# AMS_Test_Board_rev1.net
KiCad netlist of a schematic drawn in EAGLE
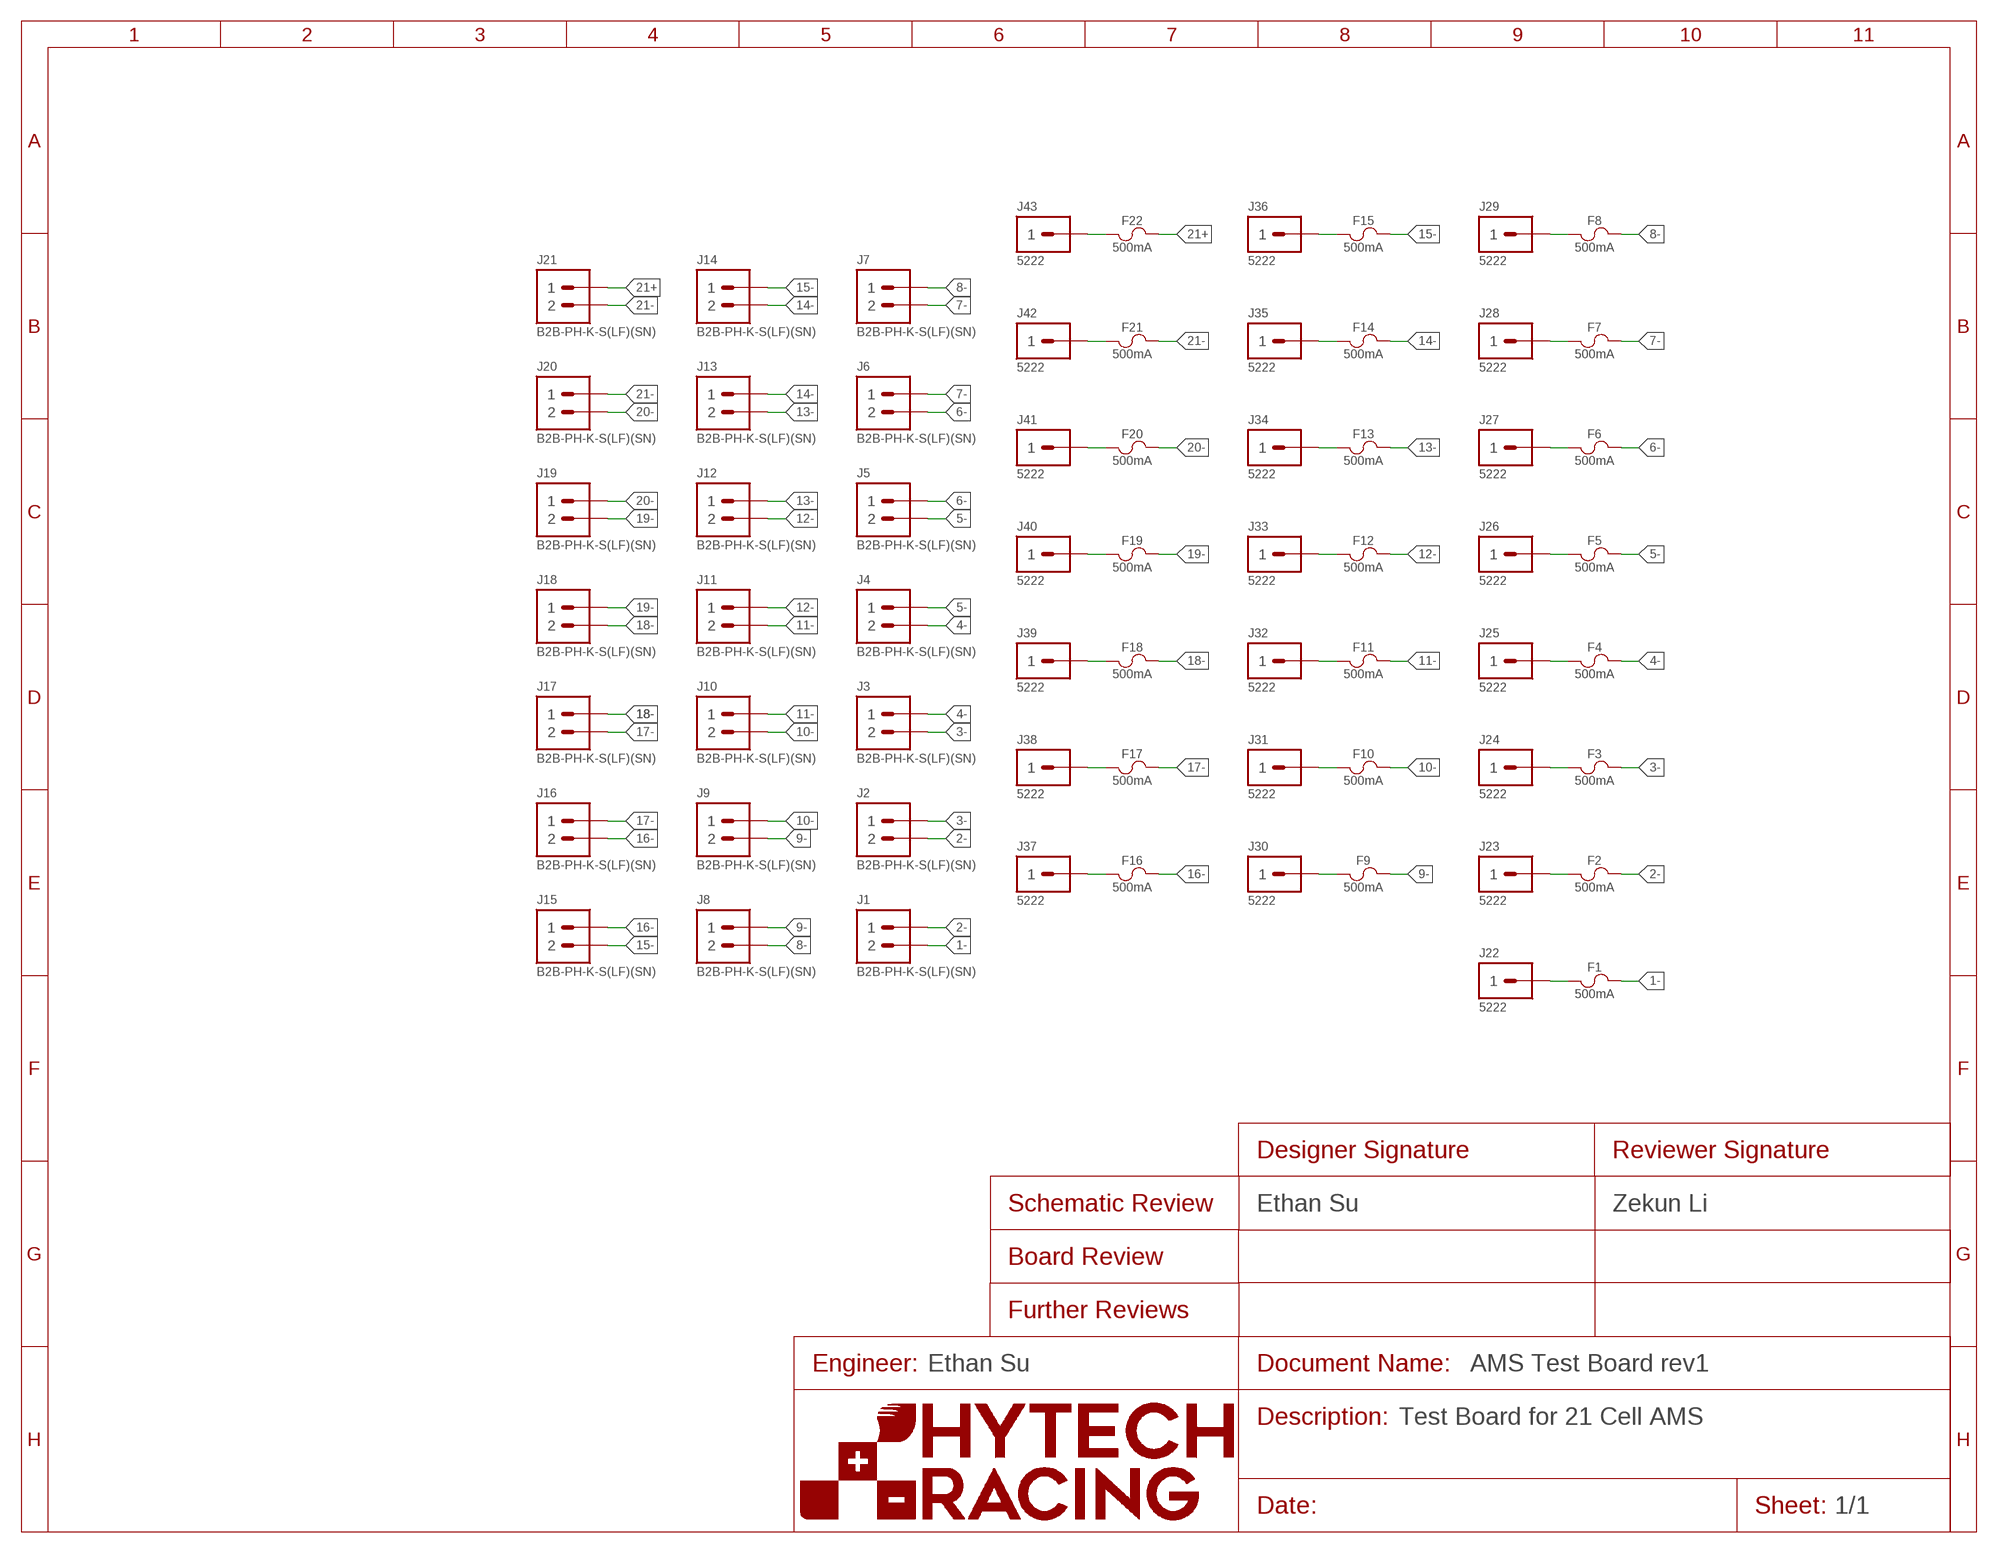
[diagram p0: schematic, sheet 1]

(export (version "E")
  (design (tool "Eeschema 10.0.6"))
  (components
    (comp (ref "F1")
      (value "FUSE_OMF_125_.5A")
      (footprint "eagle-import:OMF_125")
      (fields
        (field (name "CURRENT") "500mA")
        (field (name "MANUFACTURER") "Schurter Inc.")
        (field (name "MPN") "3404.0045.11")
        (field (name "VOLTAGE") "125V")
      )
      (libsource (lib "eagle-import") (part "FUSE_?_OMF_125.5A"))
    )
    (comp (ref "F2")
      (value "FUSE_OMF_125_.5A")
      (footprint "eagle-import:OMF_125")
      (fields
        (field (name "CURRENT") "500mA")
        (field (name "MANUFACTURER") "Schurter Inc.")
        (field (name "MPN") "3404.0045.11")
        (field (name "VOLTAGE") "125V")
      )
      (libsource (lib "eagle-import") (part "FUSE_?_OMF_125.5A"))
    )
    (comp (ref "F3")
      (value "FUSE_OMF_125_.5A")
      (footprint "eagle-import:OMF_125")
      (fields
        (field (name "CURRENT") "500mA")
        (field (name "MANUFACTURER") "Schurter Inc.")
        (field (name "MPN") "3404.0045.11")
        (field (name "VOLTAGE") "125V")
      )
      (libsource (lib "eagle-import") (part "FUSE_?_OMF_125.5A"))
    )
    (comp (ref "F4")
      (value "FUSE_OMF_125_.5A")
      (footprint "eagle-import:OMF_125")
      (fields
        (field (name "CURRENT") "500mA")
        (field (name "MANUFACTURER") "Schurter Inc.")
        (field (name "MPN") "3404.0045.11")
        (field (name "VOLTAGE") "125V")
      )
      (libsource (lib "eagle-import") (part "FUSE_?_OMF_125.5A"))
    )
    (comp (ref "F5")
      (value "FUSE_OMF_125_.5A")
      (footprint "eagle-import:OMF_125")
      (fields
        (field (name "CURRENT") "500mA")
        (field (name "MANUFACTURER") "Schurter Inc.")
        (field (name "MPN") "3404.0045.11")
        (field (name "VOLTAGE") "125V")
      )
      (libsource (lib "eagle-import") (part "FUSE_?_OMF_125.5A"))
    )
    (comp (ref "F6")
      (value "FUSE_OMF_125_.5A")
      (footprint "eagle-import:OMF_125")
      (fields
        (field (name "CURRENT") "500mA")
        (field (name "MANUFACTURER") "Schurter Inc.")
        (field (name "MPN") "3404.0045.11")
        (field (name "VOLTAGE") "125V")
      )
      (libsource (lib "eagle-import") (part "FUSE_?_OMF_125.5A"))
    )
    (comp (ref "F7")
      (value "FUSE_OMF_125_.5A")
      (footprint "eagle-import:OMF_125")
      (fields
        (field (name "CURRENT") "500mA")
        (field (name "MANUFACTURER") "Schurter Inc.")
        (field (name "MPN") "3404.0045.11")
        (field (name "VOLTAGE") "125V")
      )
      (libsource (lib "eagle-import") (part "FUSE_?_OMF_125.5A"))
    )
    (comp (ref "F8")
      (value "FUSE_OMF_125_.5A")
      (footprint "eagle-import:OMF_125")
      (fields
        (field (name "CURRENT") "500mA")
        (field (name "MANUFACTURER") "Schurter Inc.")
        (field (name "MPN") "3404.0045.11")
        (field (name "VOLTAGE") "125V")
      )
      (libsource (lib "eagle-import") (part "FUSE_?_OMF_125.5A"))
    )
    (comp (ref "F9")
      (value "FUSE_OMF_125_.5A")
      (footprint "eagle-import:OMF_125")
      (fields
        (field (name "CURRENT") "500mA")
        (field (name "MANUFACTURER") "Schurter Inc.")
        (field (name "MPN") "3404.0045.11")
        (field (name "VOLTAGE") "125V")
      )
      (libsource (lib "eagle-import") (part "FUSE_?_OMF_125.5A"))
    )
    (comp (ref "F10")
      (value "FUSE_OMF_125_.5A")
      (footprint "eagle-import:OMF_125")
      (fields
        (field (name "CURRENT") "500mA")
        (field (name "MANUFACTURER") "Schurter Inc.")
        (field (name "MPN") "3404.0045.11")
        (field (name "VOLTAGE") "125V")
      )
      (libsource (lib "eagle-import") (part "FUSE_?_OMF_125.5A"))
    )
    (comp (ref "F11")
      (value "FUSE_OMF_125_.5A")
      (footprint "eagle-import:OMF_125")
      (fields
        (field (name "CURRENT") "500mA")
        (field (name "MANUFACTURER") "Schurter Inc.")
        (field (name "MPN") "3404.0045.11")
        (field (name "VOLTAGE") "125V")
      )
      (libsource (lib "eagle-import") (part "FUSE_?_OMF_125.5A"))
    )
    (comp (ref "F12")
      (value "FUSE_OMF_125_.5A")
      (footprint "eagle-import:OMF_125")
      (fields
        (field (name "CURRENT") "500mA")
        (field (name "MANUFACTURER") "Schurter Inc.")
        (field (name "MPN") "3404.0045.11")
        (field (name "VOLTAGE") "125V")
      )
      (libsource (lib "eagle-import") (part "FUSE_?_OMF_125.5A"))
    )
    (comp (ref "F13")
      (value "FUSE_OMF_125_.5A")
      (footprint "eagle-import:OMF_125")
      (fields
        (field (name "CURRENT") "500mA")
        (field (name "MANUFACTURER") "Schurter Inc.")
        (field (name "MPN") "3404.0045.11")
        (field (name "VOLTAGE") "125V")
      )
      (libsource (lib "eagle-import") (part "FUSE_?_OMF_125.5A"))
    )
    (comp (ref "F14")
      (value "FUSE_OMF_125_.5A")
      (footprint "eagle-import:OMF_125")
      (fields
        (field (name "CURRENT") "500mA")
        (field (name "MANUFACTURER") "Schurter Inc.")
        (field (name "MPN") "3404.0045.11")
        (field (name "VOLTAGE") "125V")
      )
      (libsource (lib "eagle-import") (part "FUSE_?_OMF_125.5A"))
    )
    (comp (ref "F15")
      (value "FUSE_OMF_125_.5A")
      (footprint "eagle-import:OMF_125")
      (fields
        (field (name "CURRENT") "500mA")
        (field (name "MANUFACTURER") "Schurter Inc.")
        (field (name "MPN") "3404.0045.11")
        (field (name "VOLTAGE") "125V")
      )
      (libsource (lib "eagle-import") (part "FUSE_?_OMF_125.5A"))
    )
    (comp (ref "F16")
      (value "FUSE_OMF_125_.5A")
      (footprint "eagle-import:OMF_125")
      (fields
        (field (name "CURRENT") "500mA")
        (field (name "MANUFACTURER") "Schurter Inc.")
        (field (name "MPN") "3404.0045.11")
        (field (name "VOLTAGE") "125V")
      )
      (libsource (lib "eagle-import") (part "FUSE_?_OMF_125.5A"))
    )
    (comp (ref "F17")
      (value "FUSE_OMF_125_.5A")
      (footprint "eagle-import:OMF_125")
      (fields
        (field (name "CURRENT") "500mA")
        (field (name "MANUFACTURER") "Schurter Inc.")
        (field (name "MPN") "3404.0045.11")
        (field (name "VOLTAGE") "125V")
      )
      (libsource (lib "eagle-import") (part "FUSE_?_OMF_125.5A"))
    )
    (comp (ref "F18")
      (value "FUSE_OMF_125_.5A")
      (footprint "eagle-import:OMF_125")
      (fields
        (field (name "CURRENT") "500mA")
        (field (name "MANUFACTURER") "Schurter Inc.")
        (field (name "MPN") "3404.0045.11")
        (field (name "VOLTAGE") "125V")
      )
      (libsource (lib "eagle-import") (part "FUSE_?_OMF_125.5A"))
    )
    (comp (ref "F19")
      (value "FUSE_OMF_125_.5A")
      (footprint "eagle-import:OMF_125")
      (fields
        (field (name "CURRENT") "500mA")
        (field (name "MANUFACTURER") "Schurter Inc.")
        (field (name "MPN") "3404.0045.11")
        (field (name "VOLTAGE") "125V")
      )
      (libsource (lib "eagle-import") (part "FUSE_?_OMF_125.5A"))
    )
    (comp (ref "F20")
      (value "FUSE_OMF_125_.5A")
      (footprint "eagle-import:OMF_125")
      (fields
        (field (name "CURRENT") "500mA")
        (field (name "MANUFACTURER") "Schurter Inc.")
        (field (name "MPN") "3404.0045.11")
        (field (name "VOLTAGE") "125V")
      )
      (libsource (lib "eagle-import") (part "FUSE_?_OMF_125.5A"))
    )
    (comp (ref "F21")
      (value "FUSE_OMF_125_.5A")
      (footprint "eagle-import:OMF_125")
      (fields
        (field (name "CURRENT") "500mA")
        (field (name "MANUFACTURER") "Schurter Inc.")
        (field (name "MPN") "3404.0045.11")
        (field (name "VOLTAGE") "125V")
      )
      (libsource (lib "eagle-import") (part "FUSE_?_OMF_125.5A"))
    )
    (comp (ref "F22")
      (value "FUSE_OMF_125_.5A")
      (footprint "eagle-import:OMF_125")
      (fields
        (field (name "CURRENT") "500mA")
        (field (name "MANUFACTURER") "Schurter Inc.")
        (field (name "MPN") "3404.0045.11")
        (field (name "VOLTAGE") "125V")
      )
      (libsource (lib "eagle-import") (part "FUSE_?_OMF_125.5A"))
    )
    (comp (ref "J1")
      (value "CONNECTOR-2__B2B-PH-K")
      (footprint "eagle-import:B2B-PH-K")
      (fields
        (field (name "MANUFACTURER") "JST Sales America Inc.")
        (field (name "MPN") "B2B-PH-K-S(LF)(SN)")
      )
      (libsource (lib "eagle-import") (part "CONNECTOR-2_?_B2B-PH-K"))
    )
    (comp (ref "J2")
      (value "CONNECTOR-2__B2B-PH-K")
      (footprint "eagle-import:B2B-PH-K")
      (fields
        (field (name "MANUFACTURER") "JST Sales America Inc.")
        (field (name "MPN") "B2B-PH-K-S(LF)(SN)")
      )
      (libsource (lib "eagle-import") (part "CONNECTOR-2_?_B2B-PH-K"))
    )
    (comp (ref "J3")
      (value "CONNECTOR-2__B2B-PH-K")
      (footprint "eagle-import:B2B-PH-K")
      (fields
        (field (name "MANUFACTURER") "JST Sales America Inc.")
        (field (name "MPN") "B2B-PH-K-S(LF)(SN)")
      )
      (libsource (lib "eagle-import") (part "CONNECTOR-2_?_B2B-PH-K"))
    )
    (comp (ref "J4")
      (value "CONNECTOR-2__B2B-PH-K")
      (footprint "eagle-import:B2B-PH-K")
      (fields
        (field (name "MANUFACTURER") "JST Sales America Inc.")
        (field (name "MPN") "B2B-PH-K-S(LF)(SN)")
      )
      (libsource (lib "eagle-import") (part "CONNECTOR-2_?_B2B-PH-K"))
    )
    (comp (ref "J5")
      (value "CONNECTOR-2__B2B-PH-K")
      (footprint "eagle-import:B2B-PH-K")
      (fields
        (field (name "MANUFACTURER") "JST Sales America Inc.")
        (field (name "MPN") "B2B-PH-K-S(LF)(SN)")
      )
      (libsource (lib "eagle-import") (part "CONNECTOR-2_?_B2B-PH-K"))
    )
    (comp (ref "J6")
      (value "CONNECTOR-2__B2B-PH-K")
      (footprint "eagle-import:B2B-PH-K")
      (fields
        (field (name "MANUFACTURER") "JST Sales America Inc.")
        (field (name "MPN") "B2B-PH-K-S(LF)(SN)")
      )
      (libsource (lib "eagle-import") (part "CONNECTOR-2_?_B2B-PH-K"))
    )
    (comp (ref "J7")
      (value "CONNECTOR-2__B2B-PH-K")
      (footprint "eagle-import:B2B-PH-K")
      (fields
        (field (name "MANUFACTURER") "JST Sales America Inc.")
        (field (name "MPN") "B2B-PH-K-S(LF)(SN)")
      )
      (libsource (lib "eagle-import") (part "CONNECTOR-2_?_B2B-PH-K"))
    )
    (comp (ref "J8")
      (value "CONNECTOR-2__B2B-PH-K")
      (footprint "eagle-import:B2B-PH-K")
      (fields
        (field (name "MANUFACTURER") "JST Sales America Inc.")
        (field (name "MPN") "B2B-PH-K-S(LF)(SN)")
      )
      (libsource (lib "eagle-import") (part "CONNECTOR-2_?_B2B-PH-K"))
    )
    (comp (ref "J9")
      (value "CONNECTOR-2__B2B-PH-K")
      (footprint "eagle-import:B2B-PH-K")
      (fields
        (field (name "MANUFACTURER") "JST Sales America Inc.")
        (field (name "MPN") "B2B-PH-K-S(LF)(SN)")
      )
      (libsource (lib "eagle-import") (part "CONNECTOR-2_?_B2B-PH-K"))
    )
    (comp (ref "J10")
      (value "CONNECTOR-2__B2B-PH-K")
      (footprint "eagle-import:B2B-PH-K")
      (fields
        (field (name "MANUFACTURER") "JST Sales America Inc.")
        (field (name "MPN") "B2B-PH-K-S(LF)(SN)")
      )
      (libsource (lib "eagle-import") (part "CONNECTOR-2_?_B2B-PH-K"))
    )
    (comp (ref "J11")
      (value "CONNECTOR-2__B2B-PH-K")
      (footprint "eagle-import:B2B-PH-K")
      (fields
        (field (name "MANUFACTURER") "JST Sales America Inc.")
        (field (name "MPN") "B2B-PH-K-S(LF)(SN)")
      )
      (libsource (lib "eagle-import") (part "CONNECTOR-2_?_B2B-PH-K"))
    )
    (comp (ref "J12")
      (value "CONNECTOR-2__B2B-PH-K")
      (footprint "eagle-import:B2B-PH-K")
      (fields
        (field (name "MANUFACTURER") "JST Sales America Inc.")
        (field (name "MPN") "B2B-PH-K-S(LF)(SN)")
      )
      (libsource (lib "eagle-import") (part "CONNECTOR-2_?_B2B-PH-K"))
    )
    (comp (ref "J13")
      (value "CONNECTOR-2__B2B-PH-K")
      (footprint "eagle-import:B2B-PH-K")
      (fields
        (field (name "MANUFACTURER") "JST Sales America Inc.")
        (field (name "MPN") "B2B-PH-K-S(LF)(SN)")
      )
      (libsource (lib "eagle-import") (part "CONNECTOR-2_?_B2B-PH-K"))
    )
    (comp (ref "J14")
      (value "CONNECTOR-2__B2B-PH-K")
      (footprint "eagle-import:B2B-PH-K")
      (fields
        (field (name "MANUFACTURER") "JST Sales America Inc.")
        (field (name "MPN") "B2B-PH-K-S(LF)(SN)")
      )
      (libsource (lib "eagle-import") (part "CONNECTOR-2_?_B2B-PH-K"))
    )
    (comp (ref "J15")
      (value "CONNECTOR-2__B2B-PH-K")
      (footprint "eagle-import:B2B-PH-K")
      (fields
        (field (name "MANUFACTURER") "JST Sales America Inc.")
        (field (name "MPN") "B2B-PH-K-S(LF)(SN)")
      )
      (libsource (lib "eagle-import") (part "CONNECTOR-2_?_B2B-PH-K"))
    )
    (comp (ref "J16")
      (value "CONNECTOR-2__B2B-PH-K")
      (footprint "eagle-import:B2B-PH-K")
      (fields
        (field (name "MANUFACTURER") "JST Sales America Inc.")
        (field (name "MPN") "B2B-PH-K-S(LF)(SN)")
      )
      (libsource (lib "eagle-import") (part "CONNECTOR-2_?_B2B-PH-K"))
    )
    (comp (ref "J17")
      (value "CONNECTOR-2__B2B-PH-K")
      (footprint "eagle-import:B2B-PH-K")
      (fields
        (field (name "MANUFACTURER") "JST Sales America Inc.")
        (field (name "MPN") "B2B-PH-K-S(LF)(SN)")
      )
      (libsource (lib "eagle-import") (part "CONNECTOR-2_?_B2B-PH-K"))
    )
    (comp (ref "J18")
      (value "CONNECTOR-2__B2B-PH-K")
      (footprint "eagle-import:B2B-PH-K")
      (fields
        (field (name "MANUFACTURER") "JST Sales America Inc.")
        (field (name "MPN") "B2B-PH-K-S(LF)(SN)")
      )
      (libsource (lib "eagle-import") (part "CONNECTOR-2_?_B2B-PH-K"))
    )
    (comp (ref "J19")
      (value "CONNECTOR-2__B2B-PH-K")
      (footprint "eagle-import:B2B-PH-K")
      (fields
        (field (name "MANUFACTURER") "JST Sales America Inc.")
        (field (name "MPN") "B2B-PH-K-S(LF)(SN)")
      )
      (libsource (lib "eagle-import") (part "CONNECTOR-2_?_B2B-PH-K"))
    )
    (comp (ref "J20")
      (value "CONNECTOR-2__B2B-PH-K")
      (footprint "eagle-import:B2B-PH-K")
      (fields
        (field (name "MANUFACTURER") "JST Sales America Inc.")
        (field (name "MPN") "B2B-PH-K-S(LF)(SN)")
      )
      (libsource (lib "eagle-import") (part "CONNECTOR-2_?_B2B-PH-K"))
    )
    (comp (ref "J21")
      (value "CONNECTOR-2__B2B-PH-K")
      (footprint "eagle-import:B2B-PH-K")
      (fields
        (field (name "MANUFACTURER") "JST Sales America Inc.")
        (field (name "MPN") "B2B-PH-K-S(LF)(SN)")
      )
      (libsource (lib "eagle-import") (part "CONNECTOR-2_?_B2B-PH-K"))
    )
    (comp (ref "J22")
      (value "CONNECTOR-1_5222")
      (footprint "eagle-import:5222")
      (fields (field (name "MPN") "5222") (field (name "MANUFACTURER") "Keystone Electronics"))
      (libsource (lib "eagle-import") (part "CONNECTOR-1_?5222"))
    )
    (comp (ref "J23")
      (value "CONNECTOR-1_5222")
      (footprint "eagle-import:5222")
      (fields (field (name "MPN") "5222") (field (name "MANUFACTURER") "Keystone Electronics"))
      (libsource (lib "eagle-import") (part "CONNECTOR-1_?5222"))
    )
    (comp (ref "J24")
      (value "CONNECTOR-1_5222")
      (footprint "eagle-import:5222")
      (fields (field (name "MPN") "5222") (field (name "MANUFACTURER") "Keystone Electronics"))
      (libsource (lib "eagle-import") (part "CONNECTOR-1_?5222"))
    )
    (comp (ref "J25")
      (value "CONNECTOR-1_5222")
      (footprint "eagle-import:5222")
      (fields (field (name "MPN") "5222") (field (name "MANUFACTURER") "Keystone Electronics"))
      (libsource (lib "eagle-import") (part "CONNECTOR-1_?5222"))
    )
    (comp (ref "J26")
      (value "CONNECTOR-1_5222")
      (footprint "eagle-import:5222")
      (fields (field (name "MPN") "5222") (field (name "MANUFACTURER") "Keystone Electronics"))
      (libsource (lib "eagle-import") (part "CONNECTOR-1_?5222"))
    )
    (comp (ref "J27")
      (value "CONNECTOR-1_5222")
      (footprint "eagle-import:5222")
      (fields (field (name "MPN") "5222") (field (name "MANUFACTURER") "Keystone Electronics"))
      (libsource (lib "eagle-import") (part "CONNECTOR-1_?5222"))
    )
    (comp (ref "J28")
      (value "CONNECTOR-1_5222")
      (footprint "eagle-import:5222")
      (fields (field (name "MPN") "5222") (field (name "MANUFACTURER") "Keystone Electronics"))
      (libsource (lib "eagle-import") (part "CONNECTOR-1_?5222"))
    )
    (comp (ref "J29")
      (value "CONNECTOR-1_5222")
      (footprint "eagle-import:5222")
      (fields (field (name "MPN") "5222") (field (name "MANUFACTURER") "Keystone Electronics"))
      (libsource (lib "eagle-import") (part "CONNECTOR-1_?5222"))
    )
    (comp (ref "J30")
      (value "CONNECTOR-1_5222")
      (footprint "eagle-import:5222")
      (fields (field (name "MPN") "5222") (field (name "MANUFACTURER") "Keystone Electronics"))
      (libsource (lib "eagle-import") (part "CONNECTOR-1_?5222"))
    )
    (comp (ref "J31")
      (value "CONNECTOR-1_5222")
      (footprint "eagle-import:5222")
      (fields (field (name "MPN") "5222") (field (name "MANUFACTURER") "Keystone Electronics"))
      (libsource (lib "eagle-import") (part "CONNECTOR-1_?5222"))
    )
    (comp (ref "J32")
      (value "CONNECTOR-1_5222")
      (footprint "eagle-import:5222")
      (fields (field (name "MPN") "5222") (field (name "MANUFACTURER") "Keystone Electronics"))
      (libsource (lib "eagle-import") (part "CONNECTOR-1_?5222"))
    )
    (comp (ref "J33")
      (value "CONNECTOR-1_5222")
      (footprint "eagle-import:5222")
      (fields (field (name "MPN") "5222") (field (name "MANUFACTURER") "Keystone Electronics"))
      (libsource (lib "eagle-import") (part "CONNECTOR-1_?5222"))
    )
    (comp (ref "J34")
      (value "CONNECTOR-1_5222")
      (footprint "eagle-import:5222")
      (fields (field (name "MPN") "5222") (field (name "MANUFACTURER") "Keystone Electronics"))
      (libsource (lib "eagle-import") (part "CONNECTOR-1_?5222"))
    )
    (comp (ref "J35")
      (value "CONNECTOR-1_5222")
      (footprint "eagle-import:5222")
      (fields (field (name "MPN") "5222") (field (name "MANUFACTURER") "Keystone Electronics"))
      (libsource (lib "eagle-import") (part "CONNECTOR-1_?5222"))
    )
    (comp (ref "J36")
      (value "CONNECTOR-1_5222")
      (footprint "eagle-import:5222")
      (fields (field (name "MPN") "5222") (field (name "MANUFACTURER") "Keystone Electronics"))
      (libsource (lib "eagle-import") (part "CONNECTOR-1_?5222"))
    )
    (comp (ref "J37")
      (value "CONNECTOR-1_5222")
      (footprint "eagle-import:5222")
      (fields (field (name "MPN") "5222") (field (name "MANUFACTURER") "Keystone Electronics"))
      (libsource (lib "eagle-import") (part "CONNECTOR-1_?5222"))
    )
    (comp (ref "J38")
      (value "CONNECTOR-1_5222")
      (footprint "eagle-import:5222")
      (fields (field (name "MPN") "5222") (field (name "MANUFACTURER") "Keystone Electronics"))
      (libsource (lib "eagle-import") (part "CONNECTOR-1_?5222"))
    )
    (comp (ref "J39")
      (value "CONNECTOR-1_5222")
      (footprint "eagle-import:5222")
      (fields (field (name "MPN") "5222") (field (name "MANUFACTURER") "Keystone Electronics"))
      (libsource (lib "eagle-import") (part "CONNECTOR-1_?5222"))
    )
    (comp (ref "J40")
      (value "CONNECTOR-1_5222")
      (footprint "eagle-import:5222")
      (fields (field (name "MPN") "5222") (field (name "MANUFACTURER") "Keystone Electronics"))
      (libsource (lib "eagle-import") (part "CONNECTOR-1_?5222"))
    )
    (comp (ref "J41")
      (value "CONNECTOR-1_5222")
      (footprint "eagle-import:5222")
      (fields (field (name "MPN") "5222") (field (name "MANUFACTURER") "Keystone Electronics"))
      (libsource (lib "eagle-import") (part "CONNECTOR-1_?5222"))
    )
    (comp (ref "J42")
      (value "CONNECTOR-1_5222")
      (footprint "eagle-import:5222")
      (fields (field (name "MPN") "5222") (field (name "MANUFACTURER") "Keystone Electronics"))
      (libsource (lib "eagle-import") (part "CONNECTOR-1_?5222"))
    )
    (comp (ref "J43")
      (value "CONNECTOR-1_5222")
      (footprint "eagle-import:5222")
      (fields (field (name "MPN") "5222") (field (name "MANUFACTURER") "Keystone Electronics"))
      (libsource (lib "eagle-import") (part "CONNECTOR-1_?5222"))
    )
  )
  (nets
    (net (code "1") (name "1-") (class "Default")
      (node (ref "F1") (pin "2") (pinfunction "2_2") (pintype "passive"))
      (node (ref "J1") (pin "2") (pinfunction "2_2") (pintype "passive"))
    )
    (net (code "2") (name "2-") (class "Default")
      (node (ref "F2") (pin "2") (pinfunction "2_2") (pintype "passive"))
      (node (ref "J1") (pin "1") (pinfunction "1_1") (pintype "passive"))
      (node (ref "J2") (pin "2") (pinfunction "2_2") (pintype "passive"))
    )
    (net (code "3") (name "3-") (class "Default")
      (node (ref "F3") (pin "2") (pinfunction "2_2") (pintype "passive"))
      (node (ref "J2") (pin "1") (pinfunction "1_1") (pintype "passive"))
      (node (ref "J3") (pin "2") (pinfunction "2_2") (pintype "passive"))
    )
    (net (code "4") (name "4-") (class "Default")
      (node (ref "F4") (pin "2") (pinfunction "2_2") (pintype "passive"))
      (node (ref "J3") (pin "1") (pinfunction "1_1") (pintype "passive"))
      (node (ref "J4") (pin "2") (pinfunction "2_2") (pintype "passive"))
    )
    (net (code "5") (name "5-") (class "Default")
      (node (ref "F5") (pin "2") (pinfunction "2_2") (pintype "passive"))
      (node (ref "J4") (pin "1") (pinfunction "1_1") (pintype "passive"))
      (node (ref "J5") (pin "2") (pinfunction "2_2") (pintype "passive"))
    )
    (net (code "6") (name "6-") (class "Default")
      (node (ref "F6") (pin "2") (pinfunction "2_2") (pintype "passive"))
      (node (ref "J5") (pin "1") (pinfunction "1_1") (pintype "passive"))
      (node (ref "J6") (pin "2") (pinfunction "2_2") (pintype "passive"))
    )
    (net (code "7") (name "7-") (class "Default")
      (node (ref "F7") (pin "2") (pinfunction "2_2") (pintype "passive"))
      (node (ref "J6") (pin "1") (pinfunction "1_1") (pintype "passive"))
      (node (ref "J7") (pin "2") (pinfunction "2_2") (pintype "passive"))
    )
    (net (code "8") (name "8-") (class "Default")
      (node (ref "F8") (pin "2") (pinfunction "2_2") (pintype "passive"))
      (node (ref "J7") (pin "1") (pinfunction "1_1") (pintype "passive"))
      (node (ref "J8") (pin "2") (pinfunction "2_2") (pintype "passive"))
    )
    (net (code "9") (name "9-") (class "Default")
      (node (ref "F9") (pin "2") (pinfunction "2_2") (pintype "passive"))
      (node (ref "J8") (pin "1") (pinfunction "1_1") (pintype "passive"))
      (node (ref "J9") (pin "2") (pinfunction "2_2") (pintype "passive"))
    )
    (net (code "10") (name "10-") (class "Default")
      (node (ref "F10") (pin "2") (pinfunction "2_2") (pintype "passive"))
      (node (ref "J10") (pin "2") (pinfunction "2_2") (pintype "passive"))
      (node (ref "J9") (pin "1") (pinfunction "1_1") (pintype "passive"))
    )
    (net (code "11") (name "11-") (class "Default")
      (node (ref "F11") (pin "2") (pinfunction "2_2") (pintype "passive"))
      (node (ref "J10") (pin "1") (pinfunction "1_1") (pintype "passive"))
      (node (ref "J11") (pin "2") (pinfunction "2_2") (pintype "passive"))
    )
    (net (code "12") (name "12-") (class "Default")
      (node (ref "F12") (pin "2") (pinfunction "2_2") (pintype "passive"))
      (node (ref "J11") (pin "1") (pinfunction "1_1") (pintype "passive"))
      (node (ref "J12") (pin "2") (pinfunction "2_2") (pintype "passive"))
    )
    (net (code "13") (name "13-") (class "Default")
      (node (ref "F13") (pin "2") (pinfunction "2_2") (pintype "passive"))
      (node (ref "J12") (pin "1") (pinfunction "1_1") (pintype "passive"))
      (node (ref "J13") (pin "2") (pinfunction "2_2") (pintype "passive"))
    )
    (net (code "14") (name "14-") (class "Default")
      (node (ref "F14") (pin "2") (pinfunction "2_2") (pintype "passive"))
      (node (ref "J13") (pin "1") (pinfunction "1_1") (pintype "passive"))
      (node (ref "J14") (pin "2") (pinfunction "2_2") (pintype "passive"))
    )
    (net (code "15") (name "15-") (class "Default")
      (node (ref "F15") (pin "2") (pinfunction "2_2") (pintype "passive"))
      (node (ref "J14") (pin "1") (pinfunction "1_1") (pintype "passive"))
      (node (ref "J15") (pin "2") (pinfunction "2_2") (pintype "passive"))
    )
    (net (code "16") (name "16-") (class "Default")
      (node (ref "F16") (pin "2") (pinfunction "2_2") (pintype "passive"))
      (node (ref "J15") (pin "1") (pinfunction "1_1") (pintype "passive"))
      (node (ref "J16") (pin "2") (pinfunction "2_2") (pintype "passive"))
    )
    (net (code "17") (name "17-") (class "Default")
      (node (ref "F17") (pin "2") (pinfunction "2_2") (pintype "passive"))
      (node (ref "J16") (pin "1") (pinfunction "1_1") (pintype "passive"))
      (node (ref "J17") (pin "2") (pinfunction "2_2") (pintype "passive"))
    )
    (net (code "18") (name "18-") (class "Default")
      (node (ref "F18") (pin "2") (pinfunction "2_2") (pintype "passive"))
      (node (ref "J17") (pin "1") (pinfunction "1_1") (pintype "passive"))
      (node (ref "J18") (pin "2") (pinfunction "2_2") (pintype "passive"))
    )
    (net (code "19") (name "19-") (class "Default")
      (node (ref "F19") (pin "2") (pinfunction "2_2") (pintype "passive"))
      (node (ref "J18") (pin "1") (pinfunction "1_1") (pintype "passive"))
      (node (ref "J19") (pin "2") (pinfunction "2_2") (pintype "passive"))
    )
    (net (code "20") (name "20-") (class "Default")
      (node (ref "F20") (pin "2") (pinfunction "2_2") (pintype "passive"))
      (node (ref "J19") (pin "1") (pinfunction "1_1") (pintype "passive"))
      (node (ref "J20") (pin "2") (pinfunction "2_2") (pintype "passive"))
    )
    (net (code "21") (name "21+") (class "Default")
      (node (ref "F22") (pin "2") (pinfunction "2_2") (pintype "passive"))
      (node (ref "J21") (pin "1") (pinfunction "1_1") (pintype "passive"))
    )
    (net (code "22") (name "21-") (class "Default")
      (node (ref "F21") (pin "2") (pinfunction "2_2") (pintype "passive"))
      (node (ref "J20") (pin "1") (pinfunction "1_1") (pintype "passive"))
      (node (ref "J21") (pin "2") (pinfunction "2_2") (pintype "passive"))
    )
    (net (code "23") (name "Net-(F1-Pad1)") (class "Default")
      (node (ref "F1") (pin "1") (pinfunction "1_1") (pintype "passive"))
      (node (ref "J22") (pin "1") (pinfunction "1_1") (pintype "passive"))
    )
    (net (code "24") (name "Net-(F2-Pad1)") (class "Default")
      (node (ref "F2") (pin "1") (pinfunction "1_1") (pintype "passive"))
      (node (ref "J23") (pin "1") (pinfunction "1_1") (pintype "passive"))
    )
    (net (code "25") (name "Net-(F3-Pad1)") (class "Default")
      (node (ref "F3") (pin "1") (pinfunction "1_1") (pintype "passive"))
      (node (ref "J24") (pin "1") (pinfunction "1_1") (pintype "passive"))
    )
    (net (code "26") (name "Net-(F4-Pad1)") (class "Default")
      (node (ref "F4") (pin "1") (pinfunction "1_1") (pintype "passive"))
      (node (ref "J25") (pin "1") (pinfunction "1_1") (pintype "passive"))
    )
    (net (code "27") (name "Net-(F5-Pad1)") (class "Default")
      (node (ref "F5") (pin "1") (pinfunction "1_1") (pintype "passive"))
      (node (ref "J26") (pin "1") (pinfunction "1_1") (pintype "passive"))
    )
    (net (code "28") (name "Net-(F6-Pad1)") (class "Default")
      (node (ref "F6") (pin "1") (pinfunction "1_1") (pintype "passive"))
      (node (ref "J27") (pin "1") (pinfunction "1_1") (pintype "passive"))
    )
    (net (code "29") (name "Net-(F7-Pad1)") (class "Default")
      (node (ref "F7") (pin "1") (pinfunction "1_1") (pintype "passive"))
      (node (ref "J28") (pin "1") (pinfunction "1_1") (pintype "passive"))
    )
    (net (code "30") (name "Net-(F8-Pad1)") (class "Default")
      (node (ref "F8") (pin "1") (pinfunction "1_1") (pintype "passive"))
      (node (ref "J29") (pin "1") (pinfunction "1_1") (pintype "passive"))
    )
    (net (code "31") (name "Net-(F9-Pad1)") (class "Default")
      (node (ref "F9") (pin "1") (pinfunction "1_1") (pintype "passive"))
      (node (ref "J30") (pin "1") (pinfunction "1_1") (pintype "passive"))
    )
    (net (code "32") (name "Net-(F10-Pad1)") (class "Default")
      (node (ref "F10") (pin "1") (pinfunction "1_1") (pintype "passive"))
      (node (ref "J31") (pin "1") (pinfunction "1_1") (pintype "passive"))
    )
    (net (code "33") (name "Net-(F11-Pad1)") (class "Default")
      (node (ref "F11") (pin "1") (pinfunction "1_1") (pintype "passive"))
      (node (ref "J32") (pin "1") (pinfunction "1_1") (pintype "passive"))
    )
    (net (code "34") (name "Net-(F12-Pad1)") (class "Default")
      (node (ref "F12") (pin "1") (pinfunction "1_1") (pintype "passive"))
      (node (ref "J33") (pin "1") (pinfunction "1_1") (pintype "passive"))
    )
    (net (code "35") (name "Net-(F13-Pad1)") (class "Default")
      (node (ref "F13") (pin "1") (pinfunction "1_1") (pintype "passive"))
      (node (ref "J34") (pin "1") (pinfunction "1_1") (pintype "passive"))
    )
    (net (code "36") (name "Net-(F14-Pad1)") (class "Default")
      (node (ref "F14") (pin "1") (pinfunction "1_1") (pintype "passive"))
      (node (ref "J35") (pin "1") (pinfunction "1_1") (pintype "passive"))
    )
    (net (code "37") (name "Net-(F15-Pad1)") (class "Default")
      (node (ref "F15") (pin "1") (pinfunction "1_1") (pintype "passive"))
      (node (ref "J36") (pin "1") (pinfunction "1_1") (pintype "passive"))
    )
    (net (code "38") (name "Net-(F16-Pad1)") (class "Default")
      (node (ref "F16") (pin "1") (pinfunction "1_1") (pintype "passive"))
      (node (ref "J37") (pin "1") (pinfunction "1_1") (pintype "passive"))
    )
    (net (code "39") (name "Net-(F17-Pad1)") (class "Default")
      (node (ref "F17") (pin "1") (pinfunction "1_1") (pintype "passive"))
      (node (ref "J38") (pin "1") (pinfunction "1_1") (pintype "passive"))
    )
    (net (code "40") (name "Net-(F18-Pad1)") (class "Default")
      (node (ref "F18") (pin "1") (pinfunction "1_1") (pintype "passive"))
      (node (ref "J39") (pin "1") (pinfunction "1_1") (pintype "passive"))
    )
    (net (code "41") (name "Net-(F19-Pad1)") (class "Default")
      (node (ref "F19") (pin "1") (pinfunction "1_1") (pintype "passive"))
      (node (ref "J40") (pin "1") (pinfunction "1_1") (pintype "passive"))
    )
    (net (code "42") (name "Net-(F20-Pad1)") (class "Default")
      (node (ref "F20") (pin "1") (pinfunction "1_1") (pintype "passive"))
      (node (ref "J41") (pin "1") (pinfunction "1_1") (pintype "passive"))
    )
    (net (code "43") (name "Net-(F21-Pad1)") (class "Default")
      (node (ref "F21") (pin "1") (pinfunction "1_1") (pintype "passive"))
      (node (ref "J42") (pin "1") (pinfunction "1_1") (pintype "passive"))
    )
    (net (code "44") (name "Net-(F22-Pad1)") (class "Default")
      (node (ref "F22") (pin "1") (pinfunction "1_1") (pintype "passive"))
      (node (ref "J43") (pin "1") (pinfunction "1_1") (pintype "passive"))
    )
  )
)
